# CompareVoltage.net
KiCad netlist of a schematic drawn in Altium Designer
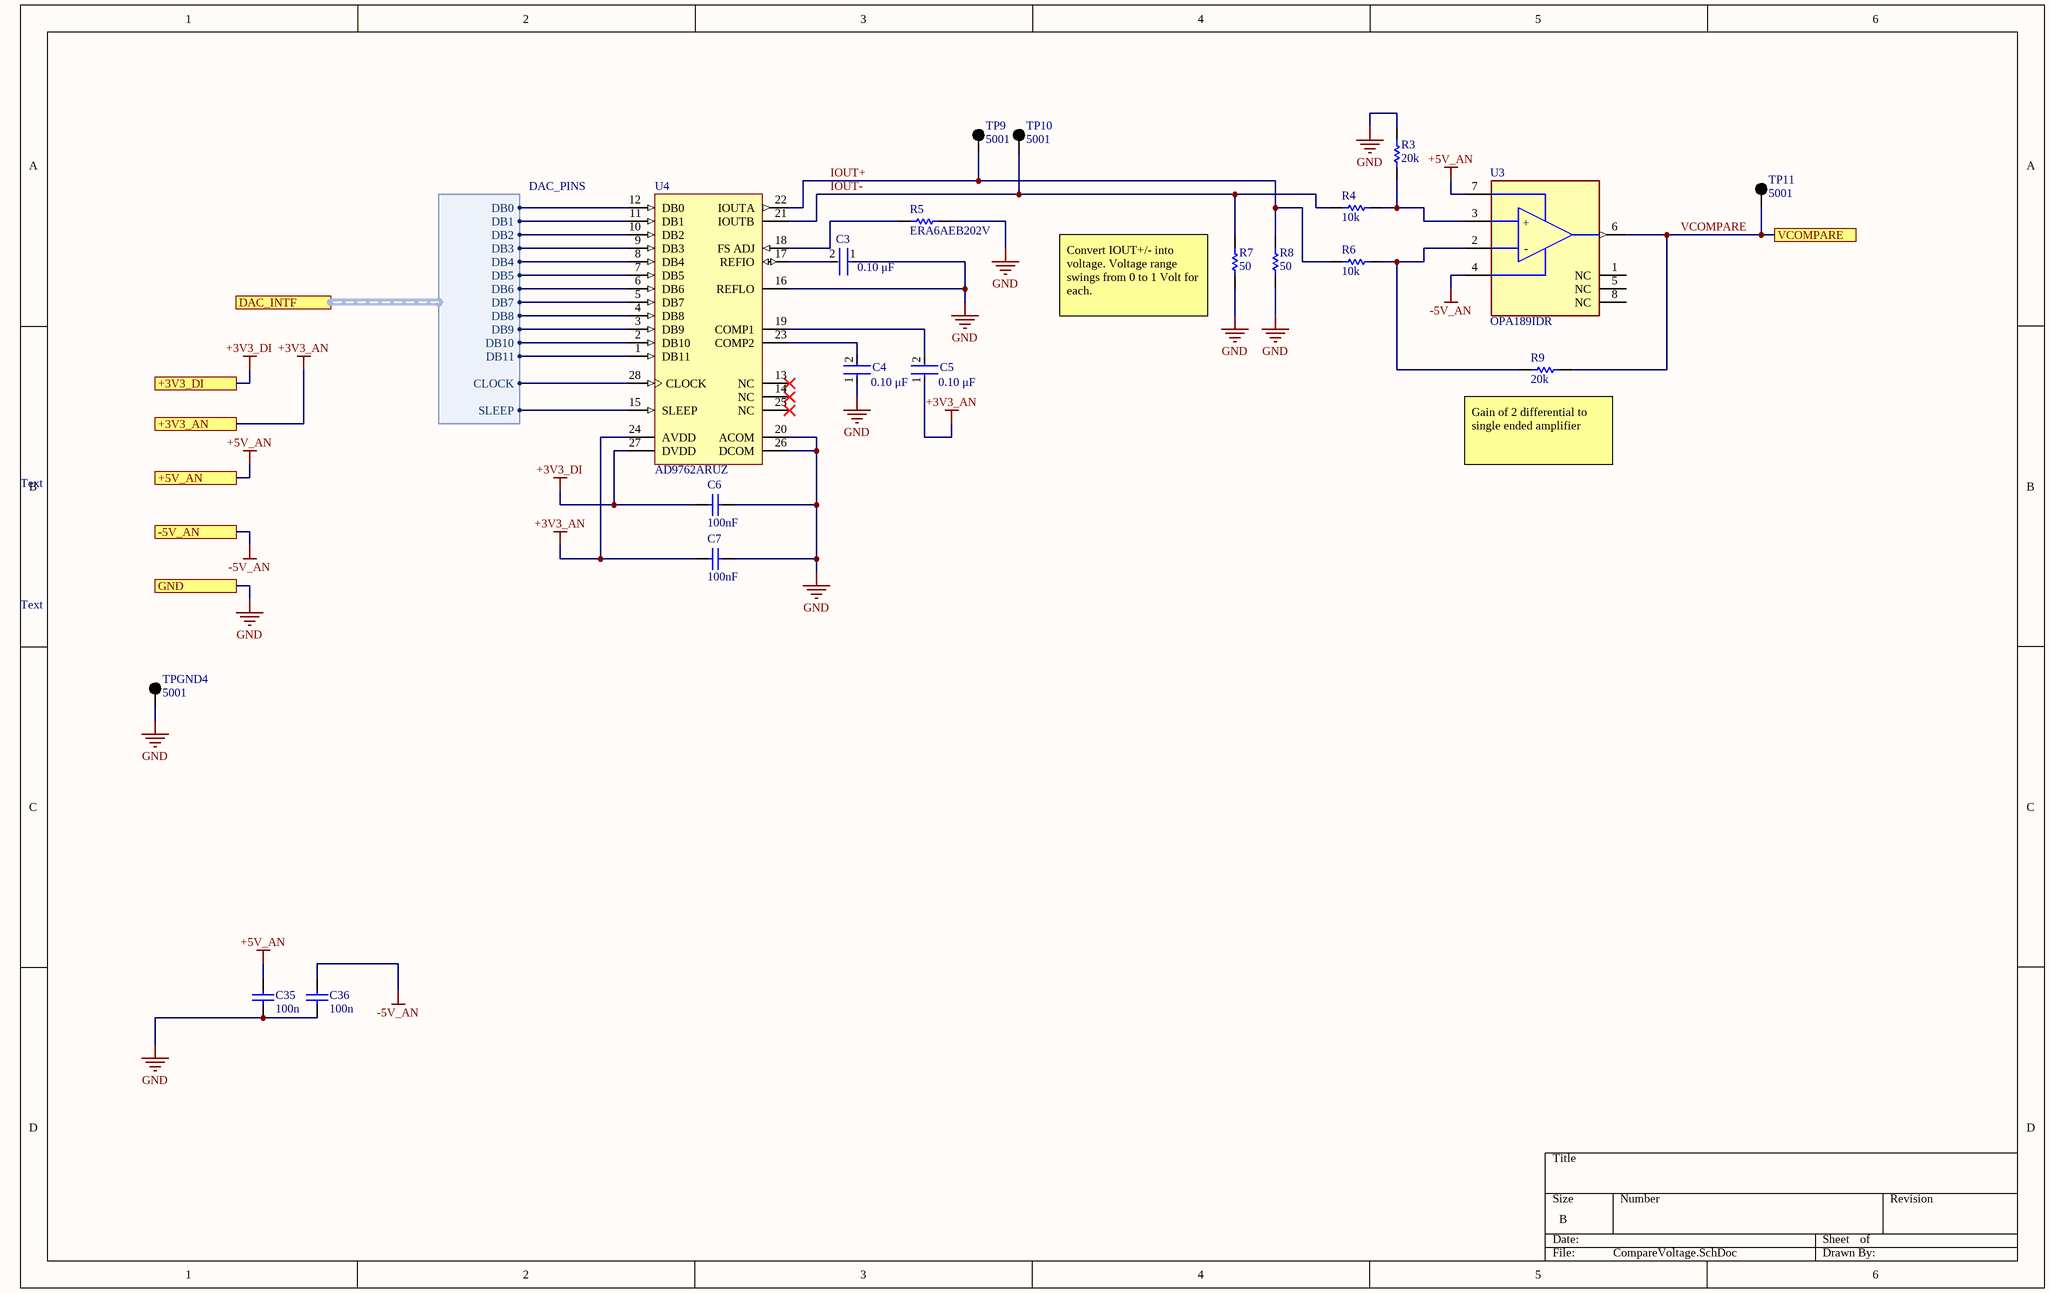
[diagram p0: CompareVoltage.SchDoc]

(export (version "E")
  (design (tool "Eeschema 10.0.6"))
  (components
    (comp (ref "C3")
      (value "0.10 μF")
      (footprint "FP-C1206C-EB-MFG")
      (description "CAP CER 0.1UF 25V 5% NP0 1206")
      (fields
        (field (name "TOLERANCE") "0.05")
        (field (name "OCTOPART") "https://octopart.com/c1206c104j3gactu-kemet-9145095")
      )
      (libsource (lib "Altium Content Vault") (part "b4654b650e69147ec39a6b967a45e02"))
    )
    (comp (ref "C4")
      (value "0.10 μF")
      (footprint "FP-C1206C-EB-MFG")
      (description "CAP CER 0.1UF 25V 5% NP0 1206")
      (fields
        (field (name "TOLERANCE") "0.05")
        (field (name "OCTOPART") "https://octopart.com/c1206c104j3gactu-kemet-9145095")
      )
      (libsource (lib "Altium Content Vault") (part "b4654b650e69147ec39a6b967a45e02"))
    )
    (comp (ref "C5")
      (value "0.10 μF")
      (footprint "FP-C1206C-EB-MFG")
      (description "CAP CER 0.1UF 25V 5% NP0 1206")
      (fields
        (field (name "TOLERANCE") "0.05")
        (field (name "OCTOPART") "https://octopart.com/c1206c104j3gactu-kemet-9145095")
      )
      (libsource (lib "Altium Content Vault") (part "b4654b650e69147ec39a6b967a45e02"))
    )
    (comp (ref "C6")
      (value "CC0603KRX7R9BB104")
      (footprint "CAPC1608X90X40ML10T20")
      (description "Chip Capacitor, 100 nF, +/- 10%, 50 V, -55 to 125 degC, 0603 (1608 Metric), RoHS, Tape and Reel")
      (fields
        (field (name "TOLERANCE") "10%")
        (field (name "CAPACITANCE") "100nF")
        (field (name "VOLTAGE") "50V")
      )
      (libsource (lib "Altium Content Vault") (part "CAP-NP-2"))
    )
    (comp (ref "C7")
      (value "CC0603KRX7R9BB104")
      (footprint "CAPC1608X90X40ML10T20")
      (description "Chip Capacitor, 100 nF, +/- 10%, 50 V, -55 to 125 degC, 0603 (1608 Metric), RoHS, Tape and Reel")
      (fields
        (field (name "TOLERANCE") "10%")
        (field (name "CAPACITANCE") "100nF")
        (field (name "VOLTAGE") "50V")
      )
      (libsource (lib "Altium Content Vault") (part "CAP-NP-2"))
    )
    (comp (ref "C35")
      (value "100n")
      (footprint "CAPC2013X88X50NL20T25")
      (fields (field (name "PART NUMBER") "C0805C104K5RACTU") (field (name "MANUFACTURER") "Kemet"))
      (libsource (lib "Altium Content Vault") (part "CAP"))
    )
    (comp (ref "C36")
      (value "100n")
      (footprint "CAPC2013X88X50NL20T25")
      (fields (field (name "PART NUMBER") "C0805C104K5RACTU") (field (name "MANUFACTURER") "Kemet"))
      (libsource (lib "Altium Content Vault") (part "CAP"))
    )
    (comp (ref "R3")
      (value "20k")
      (footprint "RESC1609X50X30LL10T20")
      (fields (field (name "MANUFACTURER") "Vishay Dale") (field (name "PART NUMBER") "CRCW060320K0FKEA"))
      (libsource (lib "Altium Content Vault") (part "RES"))
    )
    (comp (ref "R4")
      (value "10k")
      (footprint "RESC1609X50X30NL8T20")
      (description "Chip Resistor, 10 KOhm, +/- 1%, 100 mW, -55 to 155 degC, 0603 (1608 Metric), RoHS, Tape and Reel")
      (fields (field (name "MANUFACTURER") "Vishay Semiconductor"))
      (libsource (lib "Altium Content Vault") (part "RES-2"))
    )
    (comp (ref "R5")
      (value "ERA6AEB202V")
      (footprint "RESC2013X60X40ML20T25")
      (fields (field (name "MANUFACTURER") "Panasonic"))
      (libsource (lib "Altium Content Vault") (part "RES"))
    )
    (comp (ref "R6")
      (value "10k")
      (footprint "RESC1609X50X30NL8T20")
      (description "Chip Resistor, 10 KOhm, +/- 1%, 100 mW, -55 to 155 degC, 0603 (1608 Metric), RoHS, Tape and Reel")
      (fields (field (name "MANUFACTURER") "Vishay Semiconductor"))
      (libsource (lib "Altium Content Vault") (part "RES-2"))
    )
    (comp (ref "R7")
      (value "CRCW060350R0FKEA")
      (footprint "RESC1609X50X30NL10T20")
      (fields (field (name "MANUFACTURER") "Vishay Dale") (field (name "RESISTANCE") "50"))
      (libsource (lib "Altium Content Vault") (part "RES"))
    )
    (comp (ref "R8")
      (value "CRCW060350R0FKEA")
      (footprint "RESC1609X50X30NL10T20")
      (fields (field (name "MANUFACTURER") "Vishay Dale") (field (name "RESISTANCE") "50"))
      (libsource (lib "Altium Content Vault") (part "RES"))
    )
    (comp (ref "R9")
      (value "20k")
      (footprint "RESC1609X50X30LL10T20")
      (fields (field (name "MANUFACTURER") "Vishay Dale") (field (name "PART NUMBER") "CRCW060320K0FKEA"))
      (libsource (lib "Altium Content Vault") (part "RES"))
    )
    (comp (ref "TP9")
      (value "5001")
      (footprint "KSTN-5001")
      (description "Test Point, Black, 1-Pin THD, RoHS, Bulk")
      (fields (field (name "MANUFACTURER") "Keystone"))
      (libsource (lib "Altium Content Vault") (part "KSTN-TP-5001"))
    )
    (comp (ref "TP10")
      (value "5001")
      (footprint "KSTN-5001")
      (description "Test Point, Black, 1-Pin THD, RoHS, Bulk")
      (fields (field (name "MANUFACTURER") "Keystone"))
      (libsource (lib "Altium Content Vault") (part "KSTN-TP-5001"))
    )
    (comp (ref "TP11")
      (value "5001")
      (footprint "KSTN-5001")
      (description "Test Point, Black, 1-Pin THD, RoHS, Bulk")
      (fields (field (name "MANUFACTURER") "Keystone"))
      (libsource (lib "Altium Content Vault") (part "KSTN-TP-5001"))
    )
    (comp (ref "TPGND4")
      (value "5001")
      (footprint "KSTN-5001")
      (description "Test Point, Black, 1-Pin THD, RoHS, Bulk")
      (fields (field (name "MANUFACTURER") "Keystone"))
      (libsource (lib "Altium Content Vault") (part "KSTN-TP-5001"))
    )
    (comp (ref "U3")
      (value "OPA189IDR")
      (footprint "FP-D0008A-MFG")
      (description "36V ZERO DRIFT OP-AMP")
      (fields
        (field (name "MANUFACTURER") "Texas Instruments")
        (field (name "OCTOPART") "https://octopart.com/opa189idr-texas+instruments-84619764")
      )
      (libsource (lib "Altium Content Vault") (part "9a41d0a33d14b2b430246fcc7c16568"))
    )
    (comp (ref "U4")
      (value "AD9762ARUZ")
      (footprint "RU-28_L")
      (description "Single 12-Bit TxDAC, 125 Msps, -40 to +85 degC, RU-28, Pb-Free, Tube")
      (fields (field (name "GENERIC PART NUMBER") "AD9762") (field (name "MANUFACTURER") "Analog Devices"))
      (libsource (lib "Altium Content Vault") (part "ADI-AD9762-RU-28"))
    )
  )
  (nets
    (net (code "2") (name "+3V3_AN") (class "Default")
      (node (ref "C5") (pin "1") (pinfunction "1_1") (pintype "passive"))
      (node (ref "C7") (pin "2") (pinfunction "2_2") (pintype "passive"))
      (node (ref "U4") (pin "24") (pinfunction "AVDD_24") (pintype "power_in"))
    )
    (net (code "3") (name "+3V3_DI") (class "Default")
      (node (ref "C6") (pin "2") (pinfunction "2_2") (pintype "passive"))
      (node (ref "U4") (pin "27") (pinfunction "DVDD_27") (pintype "power_in"))
    )
    (net (code "4") (name "+5V_AN") (class "Default")
      (node (ref "C35") (pin "2") (pinfunction "2_2") (pintype "passive"))
      (node (ref "U3") (pin "7") (pinfunction "V+_7") (pintype "power_in"))
    )
    (net (code "5") (name "-5V_AN") (class "Default")
      (node (ref "C36") (pin "2") (pinfunction "2_2") (pintype "passive"))
      (node (ref "U3") (pin "4") (pinfunction "V-_4") (pintype "power_in"))
    )
    (net (code "6") (name "/CLOCK") (class "Default")
      (node (ref "U4") (pin "28") (pinfunction "CLOCK_28") (pintype "input"))
    )
    (net (code "7") (name "/DB0") (class "Default")
      (node (ref "U4") (pin "12") (pinfunction "DB0_12") (pintype "input"))
    )
    (net (code "8") (name "/DB1") (class "Default")
      (node (ref "U4") (pin "11") (pinfunction "DB1_11") (pintype "input"))
    )
    (net (code "9") (name "/DB2") (class "Default")
      (node (ref "U4") (pin "10") (pinfunction "DB2_10") (pintype "input"))
    )
    (net (code "10") (name "/DB3") (class "Default")
      (node (ref "U4") (pin "9") (pinfunction "DB3_9") (pintype "input"))
    )
    (net (code "11") (name "/DB4") (class "Default")
      (node (ref "U4") (pin "8") (pinfunction "DB4_8") (pintype "input"))
    )
    (net (code "12") (name "/DB5") (class "Default")
      (node (ref "U4") (pin "7") (pinfunction "DB5_7") (pintype "input"))
    )
    (net (code "13") (name "/DB6") (class "Default")
      (node (ref "U4") (pin "6") (pinfunction "DB6_6") (pintype "input"))
    )
    (net (code "14") (name "/DB7") (class "Default")
      (node (ref "U4") (pin "5") (pinfunction "DB7_5") (pintype "input"))
    )
    (net (code "15") (name "/DB8") (class "Default")
      (node (ref "U4") (pin "4") (pinfunction "DB8_4") (pintype "input"))
    )
    (net (code "16") (name "/DB9") (class "Default")
      (node (ref "U4") (pin "3") (pinfunction "DB9_3") (pintype "input"))
    )
    (net (code "17") (name "/DB10") (class "Default")
      (node (ref "U4") (pin "2") (pinfunction "DB10_2") (pintype "input"))
    )
    (net (code "18") (name "/DB11") (class "Default")
      (node (ref "U4") (pin "1") (pinfunction "DB11_1") (pintype "input"))
    )
    (net (code "19") (name "/IOUT+") (class "Default")
      (node (ref "R6") (pin "1") (pinfunction "1_1") (pintype "passive"))
      (node (ref "R8") (pin "2") (pinfunction "2_2") (pintype "passive"))
      (node (ref "TP9") (pin "1") (pintype "passive"))
      (node (ref "U4") (pin "22") (pinfunction "IOUTA_22") (pintype "output"))
    )
    (net (code "20") (name "/IOUT-") (class "Default")
      (node (ref "R4") (pin "1") (pinfunction "1_1") (pintype "passive"))
      (node (ref "R7") (pin "2") (pinfunction "2_2") (pintype "passive"))
      (node (ref "TP10") (pin "1") (pintype "passive"))
      (node (ref "U4") (pin "21") (pinfunction "IOUTB_21") (pintype "passive"))
    )
    (net (code "21") (name "/SLEEP") (class "Default")
      (node (ref "U4") (pin "15") (pinfunction "SLEEP_15") (pintype "input"))
    )
    (net (code "22") (name "/VCOMPARE") (class "Default")
      (node (ref "R9") (pin "2") (pinfunction "2_2") (pintype "passive"))
      (node (ref "TP11") (pin "1") (pintype "passive"))
      (node (ref "U3") (pin "6") (pinfunction "OUT_6") (pintype "output"))
    )
    (net (code "24") (name "GND") (class "Default")
      (node (ref "C3") (pin "1") (pinfunction "1_1") (pintype "passive"))
      (node (ref "C35") (pin "1") (pinfunction "1_1") (pintype "passive"))
      (node (ref "C36") (pin "1") (pinfunction "1_1") (pintype "passive"))
      (node (ref "C4") (pin "1") (pinfunction "1_1") (pintype "passive"))
      (node (ref "C6") (pin "1") (pinfunction "1_1") (pintype "passive"))
      (node (ref "C7") (pin "1") (pinfunction "1_1") (pintype "passive"))
      (node (ref "R3") (pin "2") (pinfunction "2_2") (pintype "passive"))
      (node (ref "R5") (pin "2") (pinfunction "2_2") (pintype "passive"))
      (node (ref "R7") (pin "1") (pinfunction "1_1") (pintype "passive"))
      (node (ref "R8") (pin "1") (pinfunction "1_1") (pintype "passive"))
      (node (ref "TPGND4") (pin "1") (pintype "passive"))
      (node (ref "U4") (pin "16") (pinfunction "REFLO_16") (pintype "passive"))
      (node (ref "U4") (pin "20") (pinfunction "ACOM_20") (pintype "power_in"))
      (node (ref "U4") (pin "26") (pinfunction "DCOM_26") (pintype "power_in"))
    )
    (net (code "25") (name "Net-(U3-+IN)") (class "Default")
      (node (ref "R3") (pin "1") (pinfunction "1_1") (pintype "passive"))
      (node (ref "R4") (pin "2") (pinfunction "2_2") (pintype "passive"))
      (node (ref "U3") (pin "3") (pinfunction "+IN_3") (pintype "tri_state"))
    )
    (net (code "26") (name "Net-(U3--IN)") (class "Default")
      (node (ref "R6") (pin "2") (pinfunction "2_2") (pintype "passive"))
      (node (ref "R9") (pin "1") (pinfunction "1_1") (pintype "passive"))
      (node (ref "U3") (pin "2") (pinfunction "-IN_2") (pintype "tri_state"))
    )
    (net (code "27") (name "Net-(U4-COMP1)") (class "Default")
      (node (ref "C5") (pin "2") (pinfunction "2_2") (pintype "passive"))
      (node (ref "U4") (pin "19") (pinfunction "COMP1_19") (pintype "passive"))
    )
    (net (code "28") (name "Net-(U4-COMP2)") (class "Default")
      (node (ref "C4") (pin "2") (pinfunction "2_2") (pintype "passive"))
      (node (ref "U4") (pin "23") (pinfunction "COMP2_23") (pintype "passive"))
    )
    (net (code "29") (name "Net-(U4-FS_ADJ)") (class "Default")
      (node (ref "R5") (pin "1") (pinfunction "1_1") (pintype "passive"))
      (node (ref "U4") (pin "18") (pinfunction "FS_ADJ_18") (pintype "input"))
    )
    (net (code "30") (name "Net-(U4-REFIO)") (class "Default")
      (node (ref "C3") (pin "2") (pinfunction "2_2") (pintype "passive"))
      (node (ref "U4") (pin "17") (pinfunction "REFIO_17") (pintype "bidirectional"))
    )
    (net (code "31") (name "unconnected-(U3-NC-Pad1)") (class "Default")
      (node (ref "U3") (pin "1") (pinfunction "NC_1") (pintype "passive"))
    )
    (net (code "32") (name "unconnected-(U3-NC-Pad5)") (class "Default")
      (node (ref "U3") (pin "5") (pinfunction "NC_5") (pintype "passive"))
    )
    (net (code "33") (name "unconnected-(U3-NC-Pad8)") (class "Default")
      (node (ref "U3") (pin "8") (pinfunction "NC_8") (pintype "passive"))
    )
    (net (code "34") (name "unconnected-(U4-NC-Pad13)") (class "Default")
      (node (ref "U4") (pin "13") (pinfunction "NC_13") (pintype "passive+no_connect"))
    )
    (net (code "35") (name "unconnected-(U4-NC-Pad14)") (class "Default")
      (node (ref "U4") (pin "14") (pinfunction "NC_14") (pintype "passive+no_connect"))
    )
    (net (code "36") (name "unconnected-(U4-NC-Pad25)") (class "Default")
      (node (ref "U4") (pin "25") (pinfunction "NC_25") (pintype "passive+no_connect"))
    )
  )
)
